# ESP32FishLightBoard.net
KiCad netlist of a schematic drawn in EAGLE
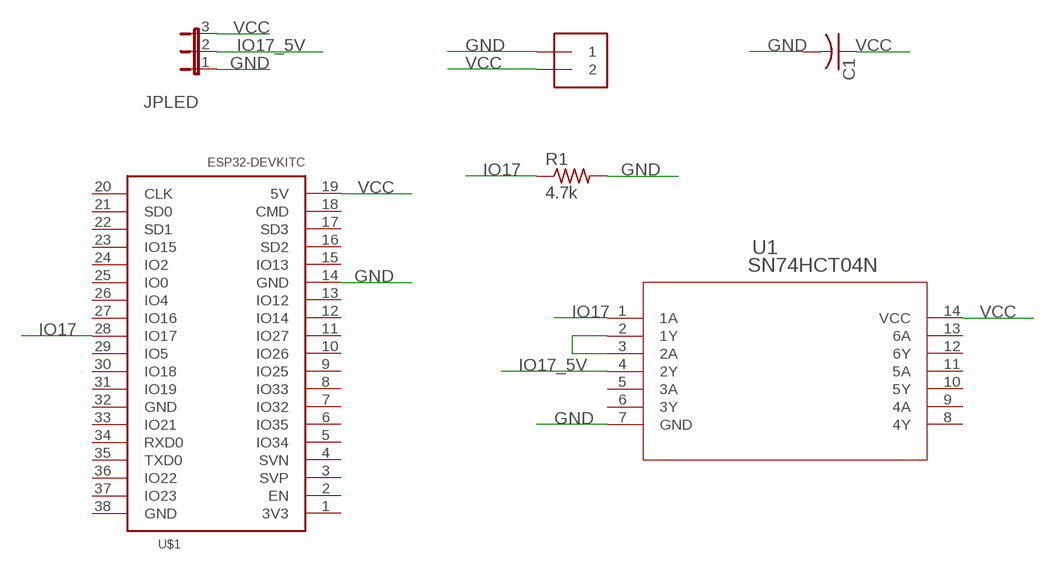
[diagram p0: schematic, sheet 1]

(export (version "E")
  (design (tool "Eeschema 10.0.6"))
  (components
    (comp (ref "C1")
      (value "C-US025-040X050")
      (footprint "eagle-import:C025-040X050")
      (libsource (lib "eagle-import") (part "C-US025-040X050"))
    )
    (comp (ref "J1")
      (value "1X2-3.5MM")
      (footprint "eagle-import:1X2-3.5MM")
      (libsource (lib "eagle-import") (part "1X2-3.5MM"))
    )
    (comp (ref "JPLED")
      (value "JP2E")
      (footprint "eagle-import:JP2")
      (libsource (lib "eagle-import") (part "JP2E"))
    )
    (comp (ref "R1")
      (value "4.7k")
      (footprint "eagle-import:0805-THM")
      (libsource (lib "eagle-import") (part "FLIPFLOP-RES"))
    )
    (comp (ref "U$1")
      (value "ESP32DEVKITC")
      (footprint "eagle-import:ESP32-DEVKITC")
      (libsource (lib "eagle-import") (part "ESP32DEVKITC"))
    )
    (comp (ref "U1")
      (value "SN74HCT04N")
      (footprint "eagle-import:N14")
      (fields
        (field (name "GENERIC_PART_NUMBER") "SN74HCT04")
        (field (name "MANUFACTURER") "Texas Instruments")
      )
      (libsource (lib "eagle-import") (part "SN74HCT04N"))
    )
  )
  (nets
    (net (code "1") (name "/GND") (class "Default")
      (node (ref "C1") (pin "2") (pinfunction "2_2") (pintype "passive"))
      (node (ref "J1") (pin "1") (pinfunction "1_1") (pintype "passive"))
      (node (ref "JPLED") (pin "1") (pinfunction "1_1") (pintype "passive"))
      (node (ref "R1") (pin "2") (pinfunction "2_2") (pintype "passive"))
      (node (ref "U$1") (pin "14") (pinfunction "GND_14") (pintype "bidirectional"))
      (node (ref "U1") (pin "7") (pinfunction "GND_7") (pintype "power_in"))
    )
    (net (code "2") (name "/IO17") (class "Default")
      (node (ref "R1") (pin "1") (pinfunction "1_1") (pintype "passive"))
      (node (ref "U$1") (pin "28") (pinfunction "IO17_28") (pintype "bidirectional"))
      (node (ref "U1") (pin "1") (pinfunction "1A_1") (pintype "input"))
    )
    (net (code "3") (name "/IO17_5V") (class "Default")
      (node (ref "JPLED") (pin "2") (pinfunction "2_2") (pintype "passive"))
      (node (ref "U1") (pin "4") (pinfunction "2Y_4") (pintype "output"))
    )
    (net (code "4") (name "/VCC") (class "Default")
      (node (ref "C1") (pin "1") (pinfunction "1_1") (pintype "passive"))
      (node (ref "J1") (pin "2") (pinfunction "2_2") (pintype "passive"))
      (node (ref "JPLED") (pin "3") (pinfunction "3_3") (pintype "passive"))
      (node (ref "U$1") (pin "19") (pinfunction "5V_19") (pintype "bidirectional"))
      (node (ref "U1") (pin "14") (pinfunction "VCC_14") (pintype "power_in"))
    )
    (net (code "5") (name "Net-(U1-1Y)") (class "Default")
      (node (ref "U1") (pin "2") (pinfunction "1Y_2") (pintype "output"))
      (node (ref "U1") (pin "3") (pinfunction "2A_3") (pintype "input"))
    )
    (net (code "6") (name "unconnected-(U$1-3V3-Pad1)") (class "Default")
      (node (ref "U$1") (pin "1") (pinfunction "3V3_1") (pintype "bidirectional"))
    )
    (net (code "7") (name "unconnected-(U$1-CLK-Pad20)") (class "Default")
      (node (ref "U$1") (pin "20") (pinfunction "CLK_20") (pintype "bidirectional"))
    )
    (net (code "8") (name "unconnected-(U$1-CMD-Pad18)") (class "Default")
      (node (ref "U$1") (pin "18") (pinfunction "CMD_18") (pintype "bidirectional"))
    )
    (net (code "9") (name "unconnected-(U$1-EN-Pad2)") (class "Default")
      (node (ref "U$1") (pin "2") (pinfunction "EN_2") (pintype "bidirectional"))
    )
    (net (code "10") (name "unconnected-(U$1-GND-Pad32)") (class "Default")
      (node (ref "U$1") (pin "32") (pinfunction "GND_32") (pintype "bidirectional"))
    )
    (net (code "11") (name "unconnected-(U$1-GND-Pad38)") (class "Default")
      (node (ref "U$1") (pin "38") (pinfunction "GND_38") (pintype "bidirectional"))
    )
    (net (code "12") (name "unconnected-(U$1-IO0-Pad25)") (class "Default")
      (node (ref "U$1") (pin "25") (pinfunction "IO0_25") (pintype "bidirectional"))
    )
    (net (code "13") (name "unconnected-(U$1-IO2-Pad24)") (class "Default")
      (node (ref "U$1") (pin "24") (pinfunction "IO2_24") (pintype "bidirectional"))
    )
    (net (code "14") (name "unconnected-(U$1-IO4-Pad26)") (class "Default")
      (node (ref "U$1") (pin "26") (pinfunction "IO4_26") (pintype "bidirectional"))
    )
    (net (code "15") (name "unconnected-(U$1-IO5-Pad29)") (class "Default")
      (node (ref "U$1") (pin "29") (pinfunction "IO5_29") (pintype "bidirectional"))
    )
    (net (code "16") (name "unconnected-(U$1-IO12-Pad13)") (class "Default")
      (node (ref "U$1") (pin "13") (pinfunction "IO12_13") (pintype "bidirectional"))
    )
    (net (code "17") (name "unconnected-(U$1-IO13-Pad15)") (class "Default")
      (node (ref "U$1") (pin "15") (pinfunction "IO13_15") (pintype "bidirectional"))
    )
    (net (code "18") (name "unconnected-(U$1-IO14-Pad12)") (class "Default")
      (node (ref "U$1") (pin "12") (pinfunction "IO14_12") (pintype "bidirectional"))
    )
    (net (code "19") (name "unconnected-(U$1-IO15-Pad23)") (class "Default")
      (node (ref "U$1") (pin "23") (pinfunction "IO15_23") (pintype "bidirectional"))
    )
    (net (code "20") (name "unconnected-(U$1-IO16-Pad27)") (class "Default")
      (node (ref "U$1") (pin "27") (pinfunction "IO16_27") (pintype "bidirectional"))
    )
    (net (code "21") (name "unconnected-(U$1-IO18-Pad30)") (class "Default")
      (node (ref "U$1") (pin "30") (pinfunction "IO18_30") (pintype "bidirectional"))
    )
    (net (code "22") (name "unconnected-(U$1-IO19-Pad31)") (class "Default")
      (node (ref "U$1") (pin "31") (pinfunction "IO19_31") (pintype "bidirectional"))
    )
    (net (code "23") (name "unconnected-(U$1-IO21-Pad33)") (class "Default")
      (node (ref "U$1") (pin "33") (pinfunction "IO21_33") (pintype "bidirectional"))
    )
    (net (code "24") (name "unconnected-(U$1-IO22-Pad36)") (class "Default")
      (node (ref "U$1") (pin "36") (pinfunction "IO22_36") (pintype "bidirectional"))
    )
    (net (code "25") (name "unconnected-(U$1-IO23-Pad37)") (class "Default")
      (node (ref "U$1") (pin "37") (pinfunction "IO23_37") (pintype "bidirectional"))
    )
    (net (code "26") (name "unconnected-(U$1-IO25-Pad9)") (class "Default")
      (node (ref "U$1") (pin "9") (pinfunction "IO25_9") (pintype "bidirectional"))
    )
    (net (code "27") (name "unconnected-(U$1-IO26-Pad10)") (class "Default")
      (node (ref "U$1") (pin "10") (pinfunction "IO26_10") (pintype "bidirectional"))
    )
    (net (code "28") (name "unconnected-(U$1-IO27-Pad11)") (class "Default")
      (node (ref "U$1") (pin "11") (pinfunction "IO27_11") (pintype "bidirectional"))
    )
    (net (code "29") (name "unconnected-(U$1-IO32-Pad7)") (class "Default")
      (node (ref "U$1") (pin "7") (pinfunction "IO32_7") (pintype "bidirectional"))
    )
    (net (code "30") (name "unconnected-(U$1-IO33-Pad8)") (class "Default")
      (node (ref "U$1") (pin "8") (pinfunction "IO33_8") (pintype "bidirectional"))
    )
    (net (code "31") (name "unconnected-(U$1-IO34-Pad5)") (class "Default")
      (node (ref "U$1") (pin "5") (pinfunction "IO34_5") (pintype "bidirectional"))
    )
    (net (code "32") (name "unconnected-(U$1-IO35-Pad6)") (class "Default")
      (node (ref "U$1") (pin "6") (pinfunction "IO35_6") (pintype "bidirectional"))
    )
    (net (code "33") (name "unconnected-(U$1-RXD0-Pad34)") (class "Default")
      (node (ref "U$1") (pin "34") (pinfunction "RXD0_34") (pintype "bidirectional"))
    )
    (net (code "34") (name "unconnected-(U$1-SD0-Pad21)") (class "Default")
      (node (ref "U$1") (pin "21") (pinfunction "SD0_21") (pintype "bidirectional"))
    )
    (net (code "35") (name "unconnected-(U$1-SD1-Pad22)") (class "Default")
      (node (ref "U$1") (pin "22") (pinfunction "SD1_22") (pintype "bidirectional"))
    )
    (net (code "36") (name "unconnected-(U$1-SD2-Pad16)") (class "Default")
      (node (ref "U$1") (pin "16") (pinfunction "SD2_16") (pintype "bidirectional"))
    )
    (net (code "37") (name "unconnected-(U$1-SD3-Pad17)") (class "Default")
      (node (ref "U$1") (pin "17") (pinfunction "SD3_17") (pintype "bidirectional"))
    )
    (net (code "38") (name "unconnected-(U$1-SVN-Pad4)") (class "Default")
      (node (ref "U$1") (pin "4") (pinfunction "SVN_4") (pintype "bidirectional"))
    )
    (net (code "39") (name "unconnected-(U$1-SVP-Pad3)") (class "Default")
      (node (ref "U$1") (pin "3") (pinfunction "SVP_3") (pintype "bidirectional"))
    )
    (net (code "40") (name "unconnected-(U$1-TXD0-Pad35)") (class "Default")
      (node (ref "U$1") (pin "35") (pinfunction "TXD0_35") (pintype "bidirectional"))
    )
    (net (code "41") (name "unconnected-(U1-3A-Pad5)") (class "Default")
      (node (ref "U1") (pin "5") (pinfunction "3A_5") (pintype "input"))
    )
    (net (code "42") (name "unconnected-(U1-3Y-Pad6)") (class "Default")
      (node (ref "U1") (pin "6") (pinfunction "3Y_6") (pintype "output"))
    )
    (net (code "43") (name "unconnected-(U1-4A-Pad9)") (class "Default")
      (node (ref "U1") (pin "9") (pinfunction "4A_9") (pintype "input"))
    )
    (net (code "44") (name "unconnected-(U1-4Y-Pad8)") (class "Default")
      (node (ref "U1") (pin "8") (pinfunction "4Y_8") (pintype "output"))
    )
    (net (code "45") (name "unconnected-(U1-5A-Pad11)") (class "Default")
      (node (ref "U1") (pin "11") (pinfunction "5A_11") (pintype "input"))
    )
    (net (code "46") (name "unconnected-(U1-5Y-Pad10)") (class "Default")
      (node (ref "U1") (pin "10") (pinfunction "5Y_10") (pintype "output"))
    )
    (net (code "47") (name "unconnected-(U1-6A-Pad13)") (class "Default")
      (node (ref "U1") (pin "13") (pinfunction "6A_13") (pintype "input"))
    )
    (net (code "48") (name "unconnected-(U1-6Y-Pad12)") (class "Default")
      (node (ref "U1") (pin "12") (pinfunction "6Y_12") (pintype "output"))
    )
  )
)
